# BT9803-150616-V2_0.net
KiCad netlist of a schematic drawn in EAGLE
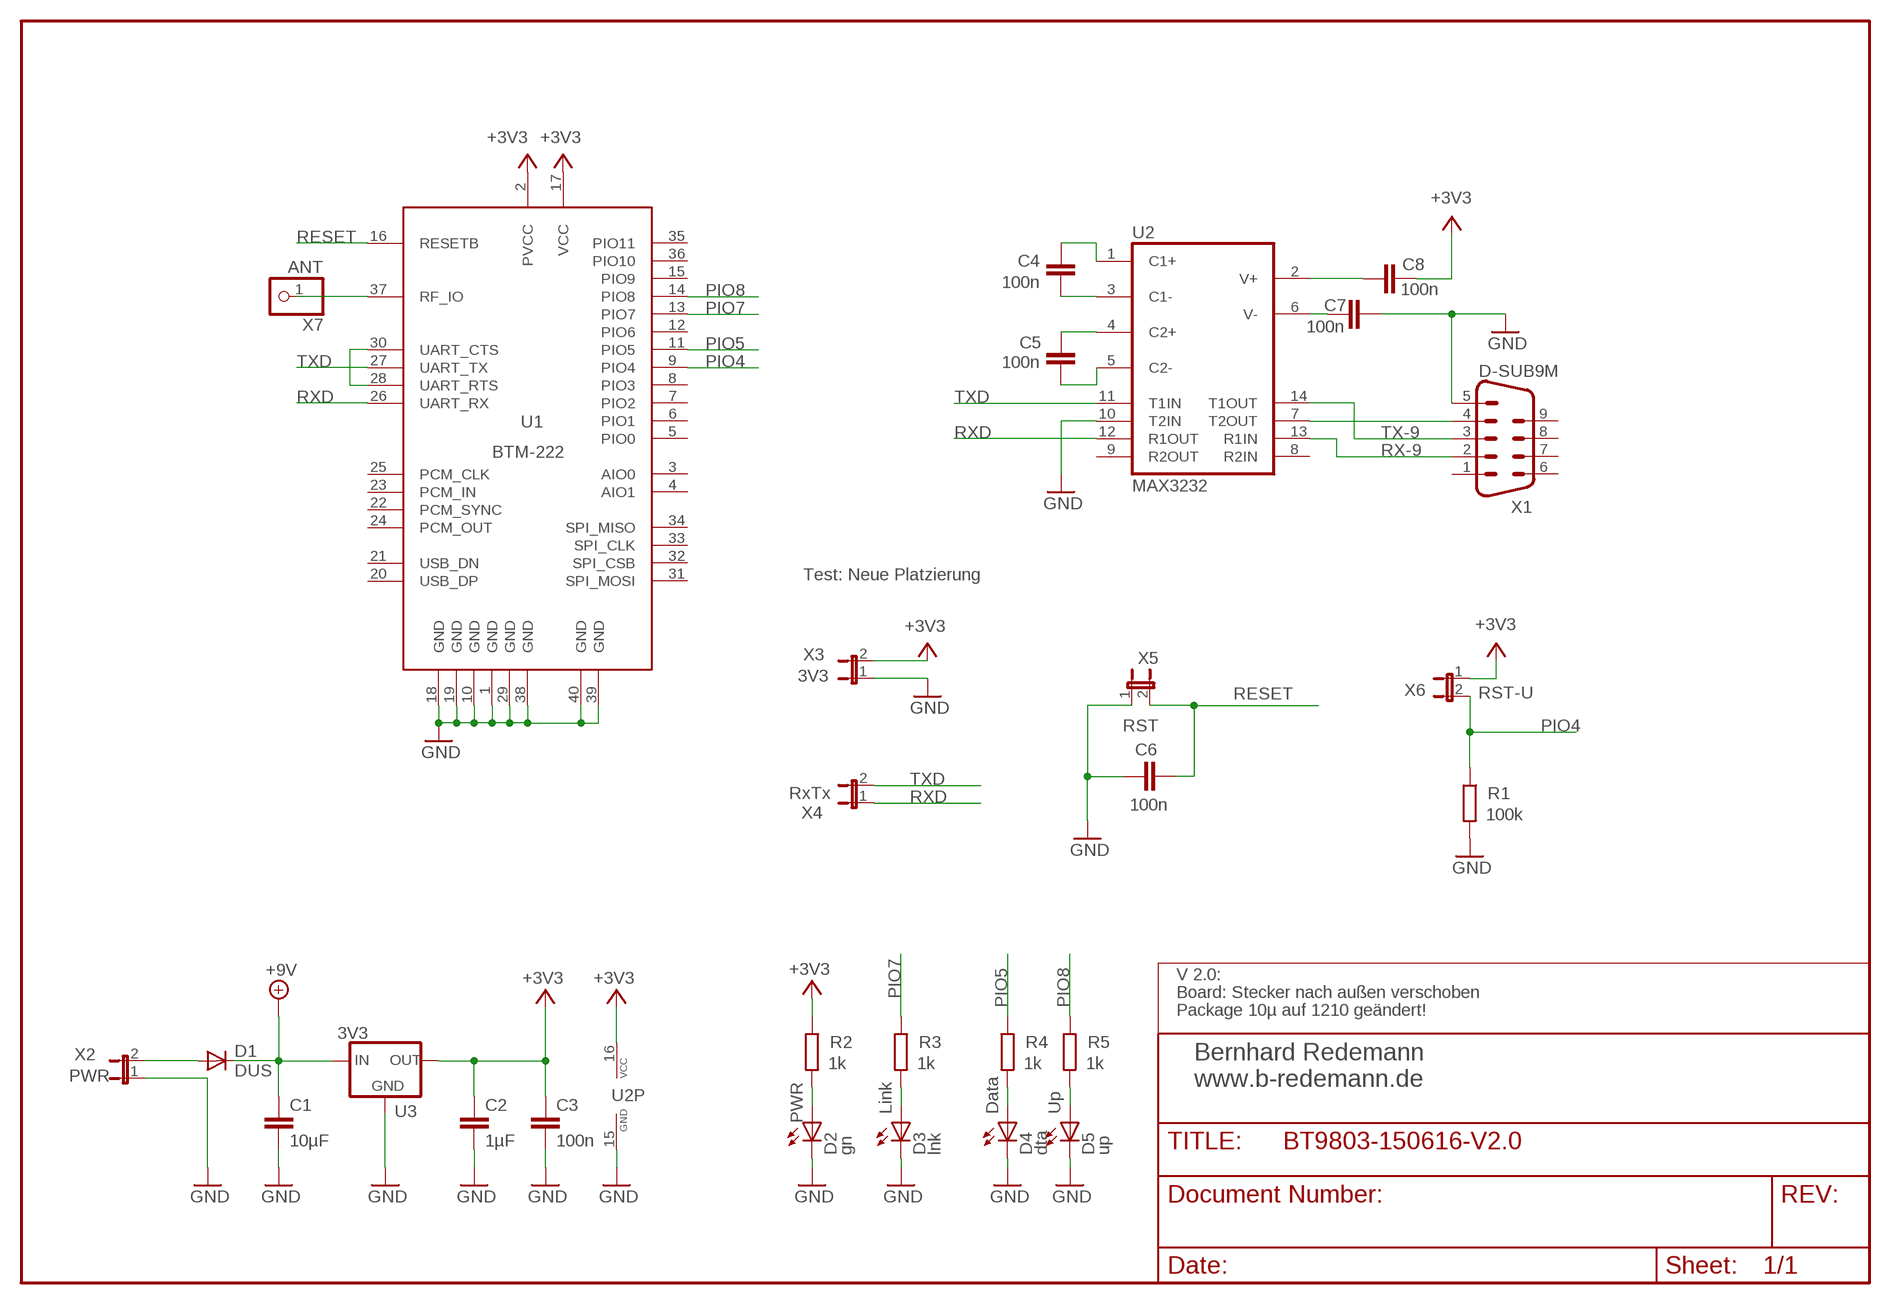
[diagram p0: schematic, sheet 1]

(export (version "E")
  (design (tool "Eeschema 10.0.6"))
  (components
    (comp (ref "C1")
      (value "10µF")
      (footprint "eagle-import:C1210")
      (libsource (lib "eagle-import") (part "C-EUC1210"))
    )
    (comp (ref "C2")
      (value "1µF")
      (footprint "eagle-import:C0805")
      (libsource (lib "eagle-import") (part "C-EUC0805"))
    )
    (comp (ref "C3")
      (value "100n")
      (footprint "eagle-import:C0805")
      (libsource (lib "eagle-import") (part "C-EUC0805"))
    )
    (comp (ref "C4")
      (value "100n")
      (footprint "eagle-import:C0805")
      (libsource (lib "eagle-import") (part "C-EUC0805"))
    )
    (comp (ref "C5")
      (value "100n")
      (footprint "eagle-import:C0805")
      (libsource (lib "eagle-import") (part "C-EUC0805"))
    )
    (comp (ref "C6")
      (value "100n")
      (footprint "eagle-import:C0805")
      (libsource (lib "eagle-import") (part "C-EUC0805"))
    )
    (comp (ref "C7")
      (value "100n")
      (footprint "eagle-import:C0805")
      (libsource (lib "eagle-import") (part "C-EUC0805"))
    )
    (comp (ref "C8")
      (value "100n")
      (footprint "eagle-import:C0805")
      (libsource (lib "eagle-import") (part "C-EUC0805"))
    )
    (comp (ref "D1")
      (value "DUS")
      (footprint "eagle-import:DO-214AC")
      (libsource (lib "eagle-import") (part "DIODE-DO-214AC"))
    )
    (comp (ref "D2")
      (value "gn")
      (footprint "eagle-import:CHIP-LED0805")
      (libsource (lib "eagle-import") (part "LEDCHIP-LED0805"))
    )
    (comp (ref "D3")
      (value "lnk")
      (footprint "eagle-import:LED3MM")
      (libsource (lib "eagle-import") (part "LED3MM"))
    )
    (comp (ref "D4")
      (value "dta")
      (footprint "eagle-import:LED3MM")
      (libsource (lib "eagle-import") (part "LED3MM"))
    )
    (comp (ref "D5")
      (value "up")
      (footprint "eagle-import:LED3MM")
      (libsource (lib "eagle-import") (part "LED3MM"))
    )
    (comp (ref "R1")
      (value "100k")
      (footprint "eagle-import:R0805")
      (libsource (lib "eagle-import") (part "R-EU_R0805"))
    )
    (comp (ref "R2")
      (value "1k")
      (footprint "eagle-import:R0805")
      (libsource (lib "eagle-import") (part "R-EU_R0805"))
    )
    (comp (ref "R3")
      (value "1k")
      (footprint "eagle-import:R0805")
      (libsource (lib "eagle-import") (part "R-EU_R0805"))
    )
    (comp (ref "R4")
      (value "1k")
      (footprint "eagle-import:R0805")
      (libsource (lib "eagle-import") (part "R-EU_R0805"))
    )
    (comp (ref "R5")
      (value "1k")
      (footprint "eagle-import:R0805")
      (libsource (lib "eagle-import") (part "R-EU_R0805"))
    )
    (comp (ref "U1")
      (value "BTM-222")
      (footprint "eagle-import:38-PIN15")
      (libsource (lib "eagle-import") (part "BTM-222"))
    )
    (comp (ref "U2")
      (value "MAX3232")
      (footprint "eagle-import:TSSOP16")
      (libsource (lib "eagle-import") (part "MAX232ECWETSSOP16"))
    )
    (comp (ref "U3")
      (value "3V3")
      (footprint "eagle-import:SOT223")
      (libsource (lib "eagle-import") (part "LM1117"))
    )
    (comp (ref "X1")
      (value "D-SUB9M")
      (footprint "eagle-import:M09D")
      (libsource (lib "eagle-import") (part "M09D"))
    )
    (comp (ref "X2")
      (value "PWR")
      (footprint "eagle-import:JP1")
      (libsource (lib "eagle-import") (part "JP1E"))
    )
    (comp (ref "X3")
      (value "3V3")
      (footprint "eagle-import:JP1")
      (libsource (lib "eagle-import") (part "JP1E"))
    )
    (comp (ref "X4")
      (value "RxTx")
      (footprint "eagle-import:JP1")
      (libsource (lib "eagle-import") (part "JP1E"))
    )
    (comp (ref "X5")
      (value "RST")
      (footprint "eagle-import:JP1")
      (libsource (lib "eagle-import") (part "JP1E"))
    )
    (comp (ref "X6")
      (value "RST-U")
      (footprint "eagle-import:JP1")
      (libsource (lib "eagle-import") (part "JP1E"))
    )
    (comp (ref "X7")
      (value "ANT")
      (footprint "eagle-import:1X01")
      (libsource (lib "eagle-import") (part "PINHD-1X1"))
    )
  )
  (nets
    (net (code "1") (name "+3V3") (class "Default")
      (node (ref "C2") (pin "1") (pinfunction "1_1") (pintype "passive"))
      (node (ref "C3") (pin "1") (pinfunction "1_1") (pintype "passive"))
      (node (ref "C8") (pin "1") (pinfunction "1_1") (pintype "passive"))
      (node (ref "R2") (pin "1") (pinfunction "1_1") (pintype "passive"))
      (node (ref "U1") (pin "17") (pinfunction "VCC_17") (pintype "power_in"))
      (node (ref "U1") (pin "2") (pinfunction "PVCC_2") (pintype "power_in"))
      (node (ref "U2") (pin "16") (pinfunction "VCC_16") (pintype "power_in"))
      (node (ref "U3") (pin "2") (pinfunction "OUT_2") (pintype "passive"))
      (node (ref "X3") (pin "2") (pinfunction "2_2") (pintype "passive"))
      (node (ref "X6") (pin "1") (pinfunction "1_1") (pintype "passive"))
    )
    (net (code "2") (name "+9V") (class "Default")
      (node (ref "C1") (pin "1") (pinfunction "1_1") (pintype "passive"))
      (node (ref "D1") (pin "C") (pinfunction "C_C") (pintype "passive"))
      (node (ref "U3") (pin "3") (pinfunction "IN_3") (pintype "input"))
    )
    (net (code "3") (name "/PIO4") (class "Default")
      (node (ref "R1") (pin "1") (pinfunction "1_1") (pintype "passive"))
      (node (ref "U1") (pin "9") (pinfunction "PIO4_9") (pintype "bidirectional"))
      (node (ref "X6") (pin "2") (pinfunction "2_2") (pintype "passive"))
    )
    (net (code "4") (name "/PIO5") (class "Default")
      (node (ref "R4") (pin "1") (pinfunction "1_1") (pintype "passive"))
      (node (ref "U1") (pin "11") (pinfunction "PIO5_11") (pintype "bidirectional"))
    )
    (net (code "5") (name "/PIO7") (class "Default")
      (node (ref "R3") (pin "1") (pinfunction "1_1") (pintype "passive"))
      (node (ref "U1") (pin "13") (pinfunction "PIO7_13") (pintype "bidirectional"))
    )
    (net (code "6") (name "/PIO8") (class "Default")
      (node (ref "R5") (pin "1") (pinfunction "1_1") (pintype "passive"))
      (node (ref "U1") (pin "14") (pinfunction "PIO8_14") (pintype "bidirectional"))
    )
    (net (code "7") (name "/RESET") (class "Default")
      (node (ref "C6") (pin "2") (pinfunction "2_2") (pintype "passive"))
      (node (ref "U1") (pin "16") (pinfunction "RESETB_16") (pintype "input"))
      (node (ref "X5") (pin "2") (pinfunction "2_2") (pintype "passive"))
    )
    (net (code "8") (name "/RX-9") (class "Default")
      (node (ref "U2") (pin "13") (pinfunction "R1IN_13") (pintype "input"))
      (node (ref "X1") (pin "2") (pinfunction "2_2") (pintype "passive"))
    )
    (net (code "9") (name "/RXD") (class "Default")
      (node (ref "U1") (pin "26") (pinfunction "UART_RX_26") (pintype "input"))
      (node (ref "U2") (pin "12") (pinfunction "R1OUT_12") (pintype "output"))
      (node (ref "X4") (pin "1") (pinfunction "1_1") (pintype "passive"))
    )
    (net (code "10") (name "/TX-9") (class "Default")
      (node (ref "U2") (pin "14") (pinfunction "T1OUT_14") (pintype "output"))
      (node (ref "X1") (pin "3") (pinfunction "3_3") (pintype "passive"))
    )
    (net (code "11") (name "/TXD") (class "Default")
      (node (ref "U1") (pin "27") (pinfunction "UART_TX_27") (pintype "output"))
      (node (ref "U2") (pin "11") (pinfunction "T1IN_11") (pintype "input"))
      (node (ref "X4") (pin "2") (pinfunction "2_2") (pintype "passive"))
    )
    (net (code "12") (name "GND") (class "Default")
      (node (ref "C1") (pin "2") (pinfunction "2_2") (pintype "passive"))
      (node (ref "C2") (pin "2") (pinfunction "2_2") (pintype "passive"))
      (node (ref "C3") (pin "2") (pinfunction "2_2") (pintype "passive"))
      (node (ref "C6") (pin "1") (pinfunction "1_1") (pintype "passive"))
      (node (ref "C7") (pin "1") (pinfunction "1_1") (pintype "passive"))
      (node (ref "D2") (pin "C") (pinfunction "C_C") (pintype "passive"))
      (node (ref "D3") (pin "K") (pinfunction "C_K") (pintype "passive"))
      (node (ref "D4") (pin "K") (pinfunction "C_K") (pintype "passive"))
      (node (ref "D5") (pin "K") (pinfunction "C_K") (pintype "passive"))
      (node (ref "R1") (pin "2") (pinfunction "2_2") (pintype "passive"))
      (node (ref "U1") (pin "1") (pinfunction "GND_1") (pintype "power_in"))
      (node (ref "U1") (pin "10") (pinfunction "GND_10") (pintype "power_in"))
      (node (ref "U1") (pin "18") (pinfunction "GND_18") (pintype "power_in"))
      (node (ref "U1") (pin "19") (pinfunction "GND_19") (pintype "power_in"))
      (node (ref "U1") (pin "29") (pinfunction "GND_29") (pintype "power_in"))
      (node (ref "U1") (pin "38") (pinfunction "GND_38") (pintype "power_in"))
      (node (ref "U1") (pin "39") (pinfunction "GND_39") (pintype "power_in"))
      (node (ref "U1") (pin "40") (pinfunction "GND_40") (pintype "power_in"))
      (node (ref "U2") (pin "10") (pinfunction "T2IN_10") (pintype "input"))
      (node (ref "U2") (pin "15") (pinfunction "GND_15") (pintype "power_in"))
      (node (ref "U3") (pin "1") (pinfunction "GND_1") (pintype "input"))
      (node (ref "X1") (pin "5") (pinfunction "5_5") (pintype "passive"))
      (node (ref "X2") (pin "1") (pinfunction "1_1") (pintype "passive"))
      (node (ref "X3") (pin "1") (pinfunction "1_1") (pintype "passive"))
      (node (ref "X5") (pin "1") (pinfunction "1_1") (pintype "passive"))
    )
    (net (code "13") (name "Net-(D1-PadA)") (class "Default")
      (node (ref "D1") (pin "A") (pinfunction "A_A") (pintype "passive"))
      (node (ref "X2") (pin "2") (pinfunction "2_2") (pintype "passive"))
    )
    (net (code "14") (name "Net-(D2-PadA)") (class "Default")
      (node (ref "D2") (pin "A") (pinfunction "A_A") (pintype "passive"))
      (node (ref "R2") (pin "2") (pinfunction "2_2") (pintype "passive"))
    )
    (net (code "15") (name "Net-(D3-PadA)") (class "Default")
      (node (ref "D3") (pin "A") (pinfunction "A_A") (pintype "passive"))
      (node (ref "R3") (pin "2") (pinfunction "2_2") (pintype "passive"))
    )
    (net (code "16") (name "Net-(D4-PadA)") (class "Default")
      (node (ref "D4") (pin "A") (pinfunction "A_A") (pintype "passive"))
      (node (ref "R4") (pin "2") (pinfunction "2_2") (pintype "passive"))
    )
    (net (code "17") (name "Net-(D5-PadA)") (class "Default")
      (node (ref "D5") (pin "A") (pinfunction "A_A") (pintype "passive"))
      (node (ref "R5") (pin "2") (pinfunction "2_2") (pintype "passive"))
    )
    (net (code "18") (name "Net-(U1-RF_IO)") (class "Default")
      (node (ref "U1") (pin "37") (pinfunction "RF_IO_37") (pintype "bidirectional"))
      (node (ref "X7") (pin "1") (pinfunction "1_1") (pintype "passive"))
    )
    (net (code "19") (name "Net-(U1-UART_CTS)") (class "Default")
      (node (ref "U1") (pin "28") (pinfunction "UART_RTS_28") (pintype "output"))
      (node (ref "U1") (pin "30") (pinfunction "UART_CTS_30") (pintype "input"))
    )
    (net (code "20") (name "Net-(U2A-C1+)") (class "Default")
      (node (ref "C4") (pin "2") (pinfunction "2_2") (pintype "passive"))
      (node (ref "U2") (pin "1") (pinfunction "C1+_1") (pintype "bidirectional"))
    )
    (net (code "21") (name "Net-(U2A-C1-)") (class "Default")
      (node (ref "C4") (pin "1") (pinfunction "1_1") (pintype "passive"))
      (node (ref "U2") (pin "3") (pinfunction "C1-_3") (pintype "bidirectional"))
    )
    (net (code "22") (name "Net-(U2A-C2+)") (class "Default")
      (node (ref "C5") (pin "2") (pinfunction "2_2") (pintype "passive"))
      (node (ref "U2") (pin "4") (pinfunction "C2+_4") (pintype "bidirectional"))
    )
    (net (code "23") (name "Net-(U2A-C2-)") (class "Default")
      (node (ref "C5") (pin "1") (pinfunction "1_1") (pintype "passive"))
      (node (ref "U2") (pin "5") (pinfunction "C2-_5") (pintype "bidirectional"))
    )
    (net (code "24") (name "Net-(U2A-T2OUT)") (class "Default")
      (node (ref "U2") (pin "7") (pinfunction "T2OUT_7") (pintype "output"))
      (node (ref "X1") (pin "4") (pinfunction "4_4") (pintype "passive"))
    )
    (net (code "25") (name "Net-(U2A-V+)") (class "Default")
      (node (ref "C8") (pin "2") (pinfunction "2_2") (pintype "passive"))
      (node (ref "U2") (pin "2") (pinfunction "V+_2") (pintype "bidirectional"))
    )
    (net (code "26") (name "Net-(U2A-V-)") (class "Default")
      (node (ref "C7") (pin "2") (pinfunction "2_2") (pintype "passive"))
      (node (ref "U2") (pin "6") (pinfunction "V-_6") (pintype "bidirectional"))
    )
    (net (code "27") (name "unconnected-(U1-AIO0-Pad3)") (class "Default")
      (node (ref "U1") (pin "3") (pinfunction "AIO0_3") (pintype "bidirectional"))
    )
    (net (code "28") (name "unconnected-(U1-AIO1-Pad4)") (class "Default")
      (node (ref "U1") (pin "4") (pinfunction "AIO1_4") (pintype "bidirectional"))
    )
    (net (code "29") (name "unconnected-(U1-PCM_CLK-Pad25)") (class "Default")
      (node (ref "U1") (pin "25") (pinfunction "PCM_CLK_25") (pintype "bidirectional"))
    )
    (net (code "30") (name "unconnected-(U1-PCM_IN-Pad23)") (class "Default")
      (node (ref "U1") (pin "23") (pinfunction "PCM_IN_23") (pintype "input"))
    )
    (net (code "31") (name "unconnected-(U1-PCM_OUT-Pad24)") (class "Default")
      (node (ref "U1") (pin "24") (pinfunction "PCM_OUT_24") (pintype "output"))
    )
    (net (code "32") (name "unconnected-(U1-PCM_SYNC-Pad22)") (class "Default")
      (node (ref "U1") (pin "22") (pinfunction "PCM_SYNC_22") (pintype "bidirectional"))
    )
    (net (code "33") (name "unconnected-(U1-PIO0-Pad5)") (class "Default")
      (node (ref "U1") (pin "5") (pinfunction "PIO0_5") (pintype "bidirectional"))
    )
    (net (code "34") (name "unconnected-(U1-PIO1-Pad6)") (class "Default")
      (node (ref "U1") (pin "6") (pinfunction "PIO1_6") (pintype "bidirectional"))
    )
    (net (code "35") (name "unconnected-(U1-PIO2-Pad7)") (class "Default")
      (node (ref "U1") (pin "7") (pinfunction "PIO2_7") (pintype "bidirectional"))
    )
    (net (code "36") (name "unconnected-(U1-PIO3-Pad8)") (class "Default")
      (node (ref "U1") (pin "8") (pinfunction "PIO3_8") (pintype "bidirectional"))
    )
    (net (code "37") (name "unconnected-(U1-PIO6-Pad12)") (class "Default")
      (node (ref "U1") (pin "12") (pinfunction "PIO6_12") (pintype "bidirectional"))
    )
    (net (code "38") (name "unconnected-(U1-PIO9-Pad15)") (class "Default")
      (node (ref "U1") (pin "15") (pinfunction "PIO9_15") (pintype "bidirectional"))
    )
    (net (code "39") (name "unconnected-(U1-PIO10-Pad36)") (class "Default")
      (node (ref "U1") (pin "36") (pinfunction "PIO10_36") (pintype "bidirectional"))
    )
    (net (code "40") (name "unconnected-(U1-PIO11-Pad35)") (class "Default")
      (node (ref "U1") (pin "35") (pinfunction "PIO11_35") (pintype "bidirectional"))
    )
    (net (code "41") (name "unconnected-(U1-SPI_CLK-Pad33)") (class "Default")
      (node (ref "U1") (pin "33") (pinfunction "SPI_CLK_33") (pintype "bidirectional"))
    )
    (net (code "42") (name "unconnected-(U1-SPI_CSB-Pad32)") (class "Default")
      (node (ref "U1") (pin "32") (pinfunction "SPI_CSB_32") (pintype "bidirectional"))
    )
    (net (code "43") (name "unconnected-(U1-SPI_MISO-Pad34)") (class "Default")
      (node (ref "U1") (pin "34") (pinfunction "SPI_MISO_34") (pintype "bidirectional"))
    )
    (net (code "44") (name "unconnected-(U1-SPI_MOSI-Pad31)") (class "Default")
      (node (ref "U1") (pin "31") (pinfunction "SPI_MOSI_31") (pintype "bidirectional"))
    )
    (net (code "45") (name "unconnected-(U1-USB_DN-Pad21)") (class "Default")
      (node (ref "U1") (pin "21") (pinfunction "USB_DN_21") (pintype "bidirectional"))
    )
    (net (code "46") (name "unconnected-(U1-USB_DP-Pad20)") (class "Default")
      (node (ref "U1") (pin "20") (pinfunction "USB_DP_20") (pintype "bidirectional"))
    )
    (net (code "47") (name "unconnected-(U2A-R2IN-Pad8)") (class "Default")
      (node (ref "U2") (pin "8") (pinfunction "R2IN_8") (pintype "input"))
    )
    (net (code "48") (name "unconnected-(U2A-R2OUT-Pad9)") (class "Default")
      (node (ref "U2") (pin "9") (pinfunction "R2OUT_9") (pintype "output"))
    )
    (net (code "49") (name "unconnected-(X1-Pad1)") (class "Default")
      (node (ref "X1") (pin "1") (pinfunction "1_1") (pintype "passive"))
    )
    (net (code "50") (name "unconnected-(X1-Pad6)") (class "Default")
      (node (ref "X1") (pin "6") (pinfunction "6_6") (pintype "passive"))
    )
    (net (code "51") (name "unconnected-(X1-Pad7)") (class "Default")
      (node (ref "X1") (pin "7") (pinfunction "7_7") (pintype "passive"))
    )
    (net (code "52") (name "unconnected-(X1-Pad8)") (class "Default")
      (node (ref "X1") (pin "8") (pinfunction "8_8") (pintype "passive"))
    )
    (net (code "53") (name "unconnected-(X1-Pad9)") (class "Default")
      (node (ref "X1") (pin "9") (pinfunction "9_9") (pintype "passive"))
    )
  )
)
